# Cerradura_electronica.net
KiCad netlist of a schematic drawn in EAGLE
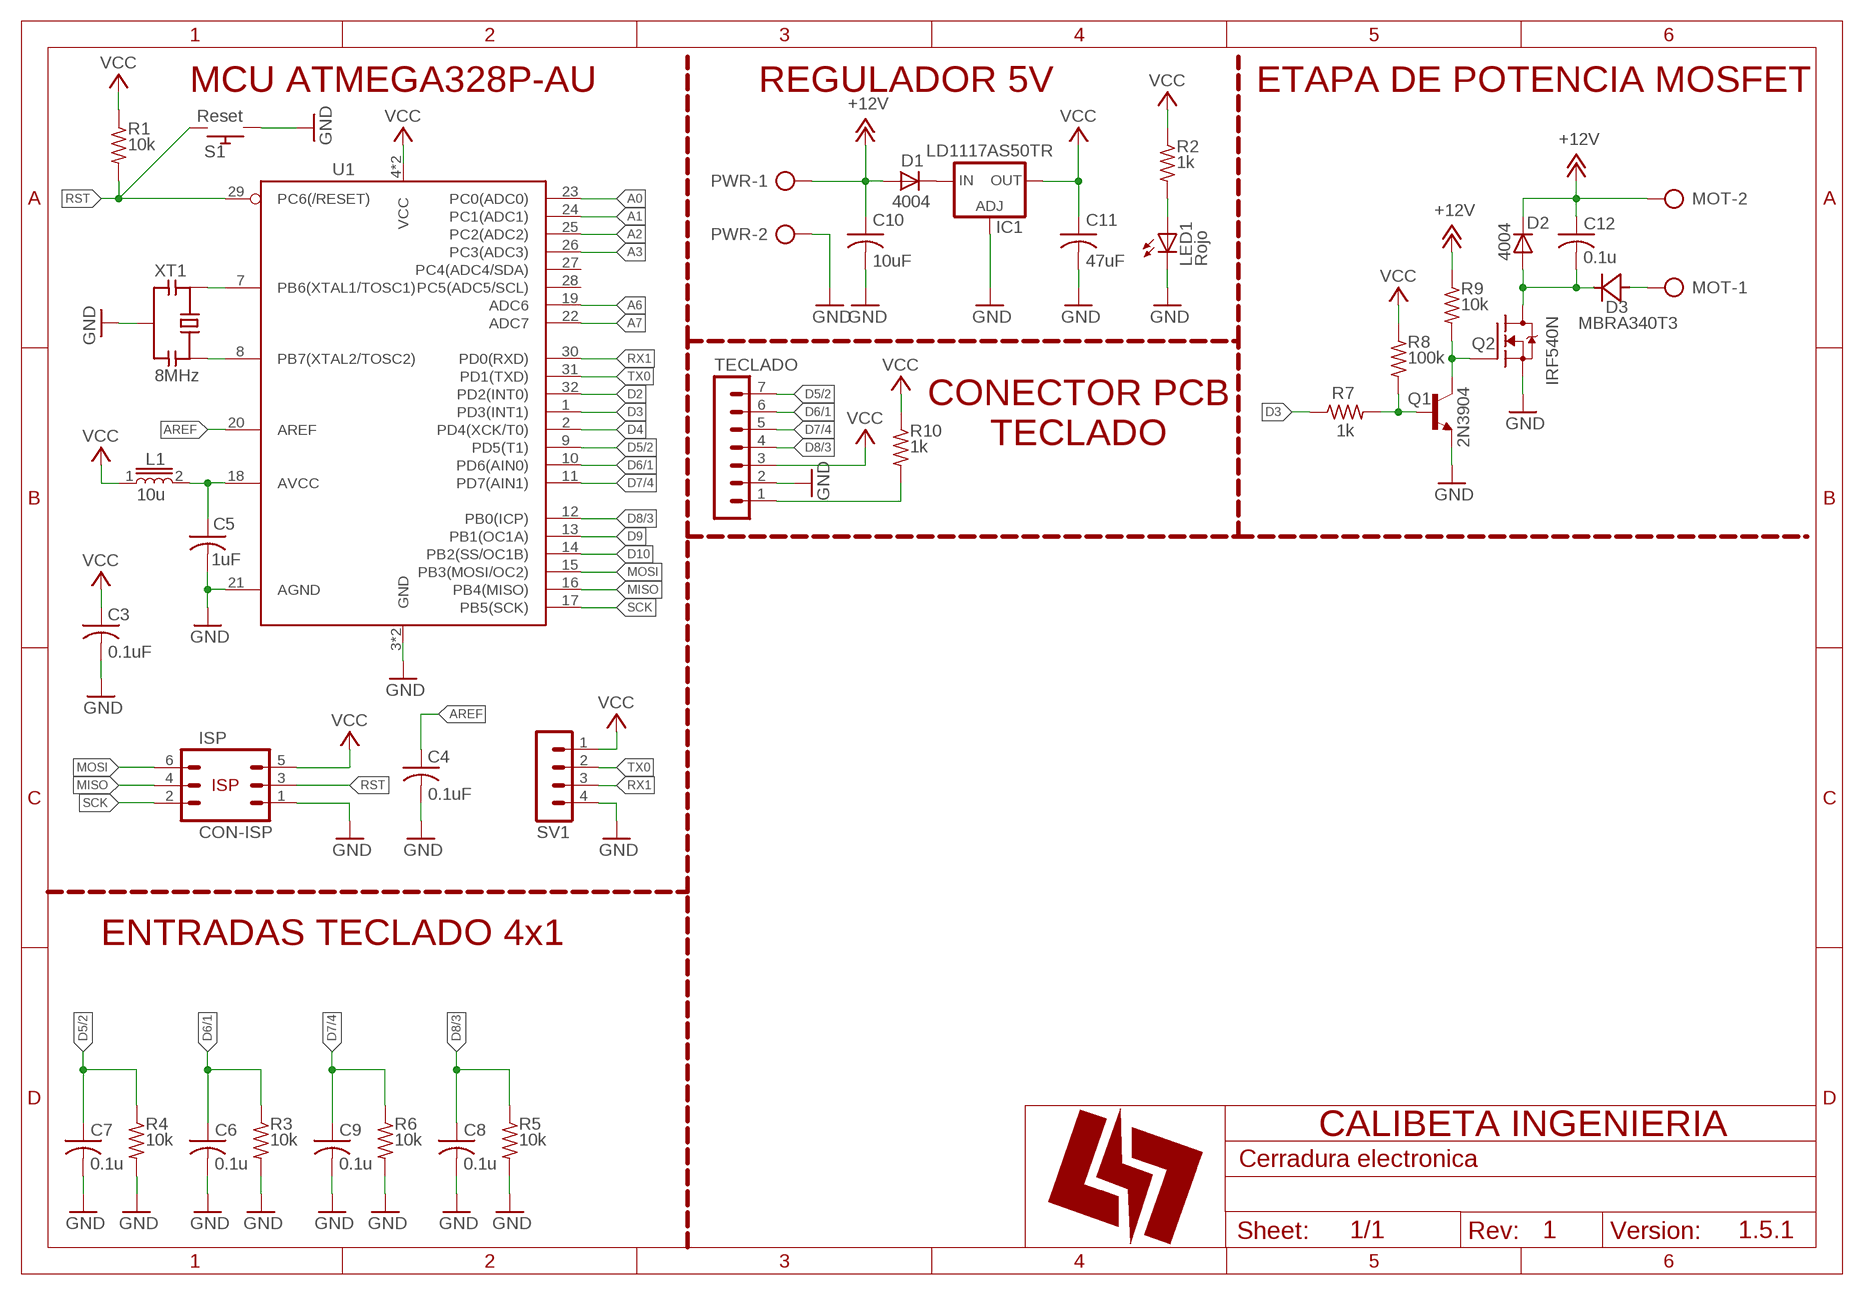
[diagram p0: schematic, sheet 1]

(export (version "E")
  (design (tool "Eeschema 10.0.6"))
  (components
    (comp (ref "C3")
      (value "0.1uF")
      (footprint "eagle-import:C0805")
      (libsource (lib "eagle-import") (part "CAPC0805"))
    )
    (comp (ref "C4")
      (value "0.1uF")
      (footprint "eagle-import:C0805")
      (libsource (lib "eagle-import") (part "CAPC0805"))
    )
    (comp (ref "C5")
      (value "1uF")
      (footprint "eagle-import:C0805")
      (libsource (lib "eagle-import") (part "CAPC0805"))
    )
    (comp (ref "C6")
      (value "0.1u")
      (footprint "eagle-import:C0805")
      (libsource (lib "eagle-import") (part "CAPC0805"))
    )
    (comp (ref "C7")
      (value "0.1u")
      (footprint "eagle-import:C0805")
      (libsource (lib "eagle-import") (part "CAPC0805"))
    )
    (comp (ref "C8")
      (value "0.1u")
      (footprint "eagle-import:C0805")
      (libsource (lib "eagle-import") (part "CAPC0805"))
    )
    (comp (ref "C9")
      (value "0.1u")
      (footprint "eagle-import:C0805")
      (libsource (lib "eagle-import") (part "CAPC0805"))
    )
    (comp (ref "C10")
      (value "10uF")
      (footprint "eagle-import:C1206")
      (libsource (lib "eagle-import") (part "CAPC1206"))
    )
    (comp (ref "C11")
      (value "47uF")
      (footprint "eagle-import:C1206")
      (libsource (lib "eagle-import") (part "CAPC1206"))
    )
    (comp (ref "C12")
      (value "0.1u")
      (footprint "eagle-import:C0805")
      (libsource (lib "eagle-import") (part "CAPC0805"))
    )
    (comp (ref "D1")
      (value "4004")
      (footprint "eagle-import:DO-214AC")
      (libsource (lib "eagle-import") (part "DIODO-DO-214AC"))
    )
    (comp (ref "D2")
      (value "4004")
      (footprint "eagle-import:DO-214AC")
      (libsource (lib "eagle-import") (part "DIODO-DO-214AC"))
    )
    (comp (ref "D3")
      (value "MBRA340T3")
      (footprint "eagle-import:SMA")
      (libsource (lib "eagle-import") (part "MBRA340T3"))
    )
    (comp (ref "IC1")
      (value "LD1117AS50TR")
      (footprint "eagle-import:SOT-223")
      (libsource (lib "eagle-import") (part "LD1117A?S50TR"))
    )
    (comp (ref "ISP")
      (value "CON-ISP")
      (footprint "eagle-import:HEADER-M2X3")
      (libsource (lib "eagle-import") (part "CON-ISP"))
    )
    (comp (ref "L1")
      (value "10u")
      (footprint "eagle-import:L0805")
      (libsource (lib "eagle-import") (part "IND-FER-L0805"))
    )
    (comp (ref "LED1")
      (value "Rojo")
      (footprint "eagle-import:LED0805-ROJO")
      (libsource (lib "eagle-import") (part "LED-ROJO0805"))
    )
    (comp (ref "MOT")
      (value "AK500-2")
      (footprint "eagle-import:AK500-2")
      (libsource (lib "eagle-import") (part "AK500-2"))
    )
    (comp (ref "PWR")
      (value "AK500-2")
      (footprint "eagle-import:AK500-2")
      (libsource (lib "eagle-import") (part "AK500-2"))
    )
    (comp (ref "Q1")
      (value "2N3904")
      (footprint "eagle-import:SOT-23_BEC")
      (libsource (lib "eagle-import") (part "SS8050"))
    )
    (comp (ref "Q2")
      (value "IRF540N")
      (footprint "eagle-import:TO-263")
      (libsource (lib "eagle-import") (part "IRF540N"))
    )
    (comp (ref "R1")
      (value "10k")
      (footprint "eagle-import:R0805")
      (libsource (lib "eagle-import") (part "RESISTOR_R0805"))
    )
    (comp (ref "R2")
      (value "1k")
      (footprint "eagle-import:R0805")
      (libsource (lib "eagle-import") (part "RESISTOR_R0805"))
    )
    (comp (ref "R3")
      (value "10k")
      (footprint "eagle-import:R0805")
      (libsource (lib "eagle-import") (part "RESISTOR_R0805"))
    )
    (comp (ref "R4")
      (value "10k")
      (footprint "eagle-import:R0805")
      (libsource (lib "eagle-import") (part "RESISTOR_R0805"))
    )
    (comp (ref "R5")
      (value "10k")
      (footprint "eagle-import:R0805")
      (libsource (lib "eagle-import") (part "RESISTOR_R0805"))
    )
    (comp (ref "R6")
      (value "10k")
      (footprint "eagle-import:R0805")
      (libsource (lib "eagle-import") (part "RESISTOR_R0805"))
    )
    (comp (ref "R7")
      (value "1k")
      (footprint "eagle-import:R0805")
      (libsource (lib "eagle-import") (part "RESISTOR_R0805"))
    )
    (comp (ref "R8")
      (value "100k")
      (footprint "eagle-import:R0805")
      (libsource (lib "eagle-import") (part "RESISTOR_R0805"))
    )
    (comp (ref "R9")
      (value "10k")
      (footprint "eagle-import:R0805")
      (libsource (lib "eagle-import") (part "RESISTOR_R0805"))
    )
    (comp (ref "R10")
      (value "1k")
      (footprint "eagle-import:R0805")
      (libsource (lib "eagle-import") (part "RESISTOR_R0805"))
    )
    (comp (ref "S1")
      (value "Reset")
      (footprint "eagle-import:ST-SMD-6X3.5MM")
      (libsource (lib "eagle-import") (part "PULSADOR-SMD-6035"))
    )
    (comp (ref "SV1")
      (value "MA04-1")
      (footprint "eagle-import:MA04-1")
      (libsource (lib "eagle-import") (part "MA04-1"))
    )
    (comp (ref "TECLADO")
      (value "MA07-1")
      (footprint "eagle-import:MA07-1")
      (libsource (lib "eagle-import") (part "MA07-1"))
    )
    (comp (ref "U$1")
      (value "A4_H-LOGO")
      (footprint "eagle-import:LOGO-10MM")
      (libsource (lib "eagle-import") (part "A4_H-LOGO"))
    )
    (comp (ref "U1")
      (value "ATMEGA328P-AU")
      (footprint "eagle-import:TQFP32")
      (libsource (lib "eagle-import") (part "ATMEGA328P-AU"))
    )
    (comp (ref "XT1")
      (value "8MHz")
      (footprint "eagle-import:3-SMD")
      (libsource (lib "eagle-import") (part "CSTNE8M00G52-R0"))
    )
  )
  (nets
    (net (code "1") (name "+12V") (class "Default")
      (node (ref "C10") (pin "1") (pinfunction "1_1") (pintype "passive"))
      (node (ref "C12") (pin "1") (pinfunction "1_1") (pintype "passive"))
      (node (ref "D1") (pin "A") (pinfunction "A_A") (pintype "passive"))
      (node (ref "D2") (pin "K") (pinfunction "C_K") (pintype "passive"))
      (node (ref "MOT") (pin "2") (pinfunction "KL1_2") (pintype "passive"))
      (node (ref "PWR") (pin "1") (pinfunction "KL1_1") (pintype "passive"))
      (node (ref "R9") (pin "1") (pinfunction "1_1") (pintype "passive"))
    )
    (net (code "2") (name "A0") (class "Default")
      (node (ref "U1") (pin "23") (pinfunction "PC0(ADC0)_23") (pintype "bidirectional"))
    )
    (net (code "3") (name "A1") (class "Default")
      (node (ref "U1") (pin "24") (pinfunction "PC1(ADC1)_24") (pintype "bidirectional"))
    )
    (net (code "4") (name "A2") (class "Default")
      (node (ref "U1") (pin "25") (pinfunction "PC2(ADC2)_25") (pintype "bidirectional"))
    )
    (net (code "5") (name "A3") (class "Default")
      (node (ref "U1") (pin "26") (pinfunction "PC3(ADC3)_26") (pintype "bidirectional"))
    )
    (net (code "6") (name "A6") (class "Default")
      (node (ref "U1") (pin "19") (pinfunction "ADC6_19") (pintype "bidirectional"))
    )
    (net (code "7") (name "A7") (class "Default")
      (node (ref "U1") (pin "22") (pinfunction "ADC7_22") (pintype "bidirectional"))
    )
    (net (code "8") (name "AREF") (class "Default")
      (node (ref "C4") (pin "1") (pinfunction "1_1") (pintype "passive"))
      (node (ref "U1") (pin "20") (pinfunction "AREF_20") (pintype "bidirectional"))
    )
    (net (code "9") (name "D2") (class "Default")
      (node (ref "U1") (pin "32") (pinfunction "PD2(INT0)_32") (pintype "bidirectional"))
    )
    (net (code "10") (name "D3") (class "Default")
      (node (ref "R7") (pin "1") (pinfunction "1_1") (pintype "passive"))
      (node (ref "U1") (pin "1") (pinfunction "PD3(INT1)_1") (pintype "bidirectional"))
    )
    (net (code "11") (name "D4") (class "Default")
      (node (ref "U1") (pin "2") (pinfunction "PD4(XCK/T0)_2") (pintype "bidirectional"))
    )
    (net (code "12") (name "D5{slash}2") (class "Default")
      (node (ref "C7") (pin "1") (pinfunction "1_1") (pintype "passive"))
      (node (ref "R4") (pin "1") (pinfunction "1_1") (pintype "passive"))
      (node (ref "TECLADO") (pin "7") (pinfunction "7_7") (pintype "passive"))
      (node (ref "U1") (pin "9") (pinfunction "PD5(T1)_9") (pintype "bidirectional"))
    )
    (net (code "13") (name "D6{slash}1") (class "Default")
      (node (ref "C6") (pin "1") (pinfunction "1_1") (pintype "passive"))
      (node (ref "R3") (pin "1") (pinfunction "1_1") (pintype "passive"))
      (node (ref "TECLADO") (pin "6") (pinfunction "6_6") (pintype "passive"))
      (node (ref "U1") (pin "10") (pinfunction "PD6(AIN0)_10") (pintype "bidirectional"))
    )
    (net (code "14") (name "D7{slash}4") (class "Default")
      (node (ref "C9") (pin "1") (pinfunction "1_1") (pintype "passive"))
      (node (ref "R6") (pin "1") (pinfunction "1_1") (pintype "passive"))
      (node (ref "TECLADO") (pin "5") (pinfunction "5_5") (pintype "passive"))
      (node (ref "U1") (pin "11") (pinfunction "PD7(AIN1)_11") (pintype "bidirectional"))
    )
    (net (code "15") (name "D8{slash}3") (class "Default")
      (node (ref "C8") (pin "1") (pinfunction "1_1") (pintype "passive"))
      (node (ref "R5") (pin "1") (pinfunction "1_1") (pintype "passive"))
      (node (ref "TECLADO") (pin "4") (pinfunction "4_4") (pintype "passive"))
      (node (ref "U1") (pin "12") (pinfunction "PB0(ICP)_12") (pintype "bidirectional"))
    )
    (net (code "16") (name "D9") (class "Default")
      (node (ref "U1") (pin "13") (pinfunction "PB1(OC1A)_13") (pintype "bidirectional"))
    )
    (net (code "17") (name "D10") (class "Default")
      (node (ref "U1") (pin "14") (pinfunction "PB2(SS/OC1B)_14") (pintype "bidirectional"))
    )
    (net (code "18") (name "GND") (class "Default")
      (node (ref "C10") (pin "2") (pinfunction "2_2") (pintype "passive"))
      (node (ref "C11") (pin "2") (pinfunction "2_2") (pintype "passive"))
      (node (ref "C3") (pin "2") (pinfunction "2_2") (pintype "passive"))
      (node (ref "C4") (pin "2") (pinfunction "2_2") (pintype "passive"))
      (node (ref "C5") (pin "2") (pinfunction "2_2") (pintype "passive"))
      (node (ref "C6") (pin "2") (pinfunction "2_2") (pintype "passive"))
      (node (ref "C7") (pin "2") (pinfunction "2_2") (pintype "passive"))
      (node (ref "C8") (pin "2") (pinfunction "2_2") (pintype "passive"))
      (node (ref "C9") (pin "2") (pinfunction "2_2") (pintype "passive"))
      (node (ref "IC1") (pin "1") (pinfunction "ADJ_1") (pintype "input"))
      (node (ref "ISP") (pin "1") (pinfunction "1_1") (pintype "passive"))
      (node (ref "LED1") (pin "C") (pinfunction "C_C") (pintype "passive"))
      (node (ref "PWR") (pin "2") (pinfunction "KL1_2") (pintype "passive"))
      (node (ref "Q1") (pin "E") (pinfunction "E_E") (pintype "passive"))
      (node (ref "Q2") (pin "3") (pinfunction "S_3") (pintype "passive"))
      (node (ref "R3") (pin "2") (pinfunction "2_2") (pintype "passive"))
      (node (ref "R4") (pin "2") (pinfunction "2_2") (pintype "passive"))
      (node (ref "R5") (pin "2") (pinfunction "2_2") (pintype "passive"))
      (node (ref "R6") (pin "2") (pinfunction "2_2") (pintype "passive"))
      (node (ref "S1") (pin "1") (pinfunction "P$1_1") (pintype "passive"))
      (node (ref "SV1") (pin "4") (pinfunction "4_4") (pintype "passive"))
      (node (ref "TECLADO") (pin "2") (pinfunction "2_2") (pintype "passive"))
      (node (ref "U1") (pin "21") (pinfunction "AGND_21") (pintype "bidirectional"))
      (node (ref "U1") (pin "3") (pinfunction "GND_3") (pintype "power_in"))
      (node (ref "U1") (pin "5") (pinfunction "GND_5") (pintype "power_in"))
      (node (ref "XT1") (pin "2") (pinfunction "GND_2") (pintype "power_in"))
    )
    (net (code "19") (name "MISO") (class "Default")
      (node (ref "ISP") (pin "4") (pinfunction "4_4") (pintype "passive"))
      (node (ref "U1") (pin "16") (pinfunction "PB4(MISO)_16") (pintype "bidirectional"))
    )
    (net (code "20") (name "MOSI") (class "Default")
      (node (ref "ISP") (pin "6") (pinfunction "6_6") (pintype "passive"))
      (node (ref "U1") (pin "15") (pinfunction "PB3(MOSI/OC2)_15") (pintype "bidirectional"))
    )
    (net (code "21") (name "Net-(D1-C)") (class "Default")
      (node (ref "D1") (pin "K") (pinfunction "C_K") (pintype "passive"))
      (node (ref "IC1") (pin "3") (pinfunction "IN_3") (pintype "input"))
    )
    (net (code "22") (name "Net-(LED1-PadA)") (class "Default")
      (node (ref "LED1") (pin "A") (pinfunction "A_A") (pintype "passive"))
      (node (ref "R2") (pin "2") (pinfunction "2_2") (pintype "passive"))
    )
    (net (code "23") (name "Net-(MOTA-KL1)") (class "Default")
      (node (ref "D3") (pin "A") (pinfunction "A_A") (pintype "passive"))
      (node (ref "MOT") (pin "1") (pinfunction "KL1_1") (pintype "passive"))
    )
    (net (code "24") (name "Net-(Q1-PadB)") (class "Default")
      (node (ref "Q1") (pin "B") (pinfunction "B_B") (pintype "passive"))
      (node (ref "R7") (pin "2") (pinfunction "2_2") (pintype "passive"))
      (node (ref "R8") (pin "2") (pinfunction "2_2") (pintype "passive"))
    )
    (net (code "25") (name "Net-(Q2-D)") (class "Default")
      (node (ref "C12") (pin "2") (pinfunction "2_2") (pintype "passive"))
      (node (ref "D2") (pin "A") (pinfunction "A_A") (pintype "passive"))
      (node (ref "D3") (pin "C") (pinfunction "C_C") (pintype "passive"))
      (node (ref "Q2") (pin "2") (pinfunction "D_2") (pintype "passive"))
    )
    (net (code "26") (name "Net-(Q2-G)") (class "Default")
      (node (ref "Q1") (pin "C") (pinfunction "C_C") (pintype "passive"))
      (node (ref "Q2") (pin "1") (pinfunction "G_1") (pintype "passive"))
      (node (ref "R9") (pin "2") (pinfunction "2_2") (pintype "passive"))
    )
    (net (code "27") (name "Net-(R10-Pad2)") (class "Default")
      (node (ref "R10") (pin "2") (pinfunction "2_2") (pintype "passive"))
      (node (ref "TECLADO") (pin "1") (pinfunction "1_1") (pintype "passive"))
    )
    (net (code "28") (name "Net-(U1-AVCC)") (class "Default")
      (node (ref "C5") (pin "1") (pinfunction "1_1") (pintype "passive"))
      (node (ref "L1") (pin "2") (pinfunction "2_2") (pintype "passive"))
      (node (ref "U1") (pin "18") (pinfunction "AVCC_18") (pintype "bidirectional"))
    )
    (net (code "29") (name "Net-(U1-PB6(XTAL1{slash}TOSC1))") (class "Default")
      (node (ref "U1") (pin "7") (pinfunction "PB6(XTAL1/TOSC1)_7") (pintype "bidirectional"))
      (node (ref "XT1") (pin "1") (pinfunction "X1_1") (pintype "bidirectional"))
    )
    (net (code "30") (name "Net-(U1-PB7(XTAL2{slash}TOSC2))") (class "Default")
      (node (ref "U1") (pin "8") (pinfunction "PB7(XTAL2/TOSC2)_8") (pintype "bidirectional"))
      (node (ref "XT1") (pin "3") (pinfunction "X2_3") (pintype "bidirectional"))
    )
    (net (code "31") (name "RST") (class "Default")
      (node (ref "ISP") (pin "3") (pinfunction "3_3") (pintype "passive"))
      (node (ref "R1") (pin "2") (pinfunction "2_2") (pintype "passive"))
      (node (ref "S1") (pin "2") (pinfunction "P$2_2") (pintype "passive"))
      (node (ref "U1") (pin "29") (pinfunction "PC6(/RESET)_29") (pintype "bidirectional"))
    )
    (net (code "32") (name "RX1") (class "Default")
      (node (ref "SV1") (pin "3") (pinfunction "3_3") (pintype "passive"))
      (node (ref "U1") (pin "30") (pinfunction "PD0(RXD)_30") (pintype "bidirectional"))
    )
    (net (code "33") (name "SCK") (class "Default")
      (node (ref "ISP") (pin "2") (pinfunction "2_2") (pintype "passive"))
      (node (ref "U1") (pin "17") (pinfunction "PB5(SCK)_17") (pintype "bidirectional"))
    )
    (net (code "34") (name "TX0") (class "Default")
      (node (ref "SV1") (pin "2") (pinfunction "2_2") (pintype "passive"))
      (node (ref "U1") (pin "31") (pinfunction "PD1(TXD)_31") (pintype "bidirectional"))
    )
    (net (code "35") (name "VCC") (class "Default")
      (node (ref "C11") (pin "1") (pinfunction "1_1") (pintype "passive"))
      (node (ref "C3") (pin "1") (pinfunction "1_1") (pintype "passive"))
      (node (ref "IC1") (pin "4") (pinfunction "OUT_4") (pintype "passive"))
      (node (ref "ISP") (pin "5") (pinfunction "5_5") (pintype "passive"))
      (node (ref "L1") (pin "1") (pinfunction "1_1") (pintype "passive"))
      (node (ref "R1") (pin "1") (pinfunction "1_1") (pintype "passive"))
      (node (ref "R10") (pin "1") (pinfunction "1_1") (pintype "passive"))
      (node (ref "R2") (pin "1") (pinfunction "1_1") (pintype "passive"))
      (node (ref "R8") (pin "1") (pinfunction "1_1") (pintype "passive"))
      (node (ref "SV1") (pin "1") (pinfunction "1_1") (pintype "passive"))
      (node (ref "TECLADO") (pin "3") (pinfunction "3_3") (pintype "passive"))
      (node (ref "U1") (pin "4") (pinfunction "VCC_4") (pintype "power_in"))
      (node (ref "U1") (pin "6") (pinfunction "VCC_6") (pintype "power_in"))
    )
    (net (code "36") (name "unconnected-(U1-PC4(ADC4{slash}SDA)-Pad27)") (class "Default")
      (node (ref "U1") (pin "27") (pinfunction "PC4(ADC4/SDA)_27") (pintype "bidirectional"))
    )
    (net (code "37") (name "unconnected-(U1-PC5(ADC5{slash}SCL)-Pad28)") (class "Default")
      (node (ref "U1") (pin "28") (pinfunction "PC5(ADC5/SCL)_28") (pintype "bidirectional"))
    )
  )
)
